# mixer-rx.net
KiCad netlist of a schematic drawn in Altium Designer
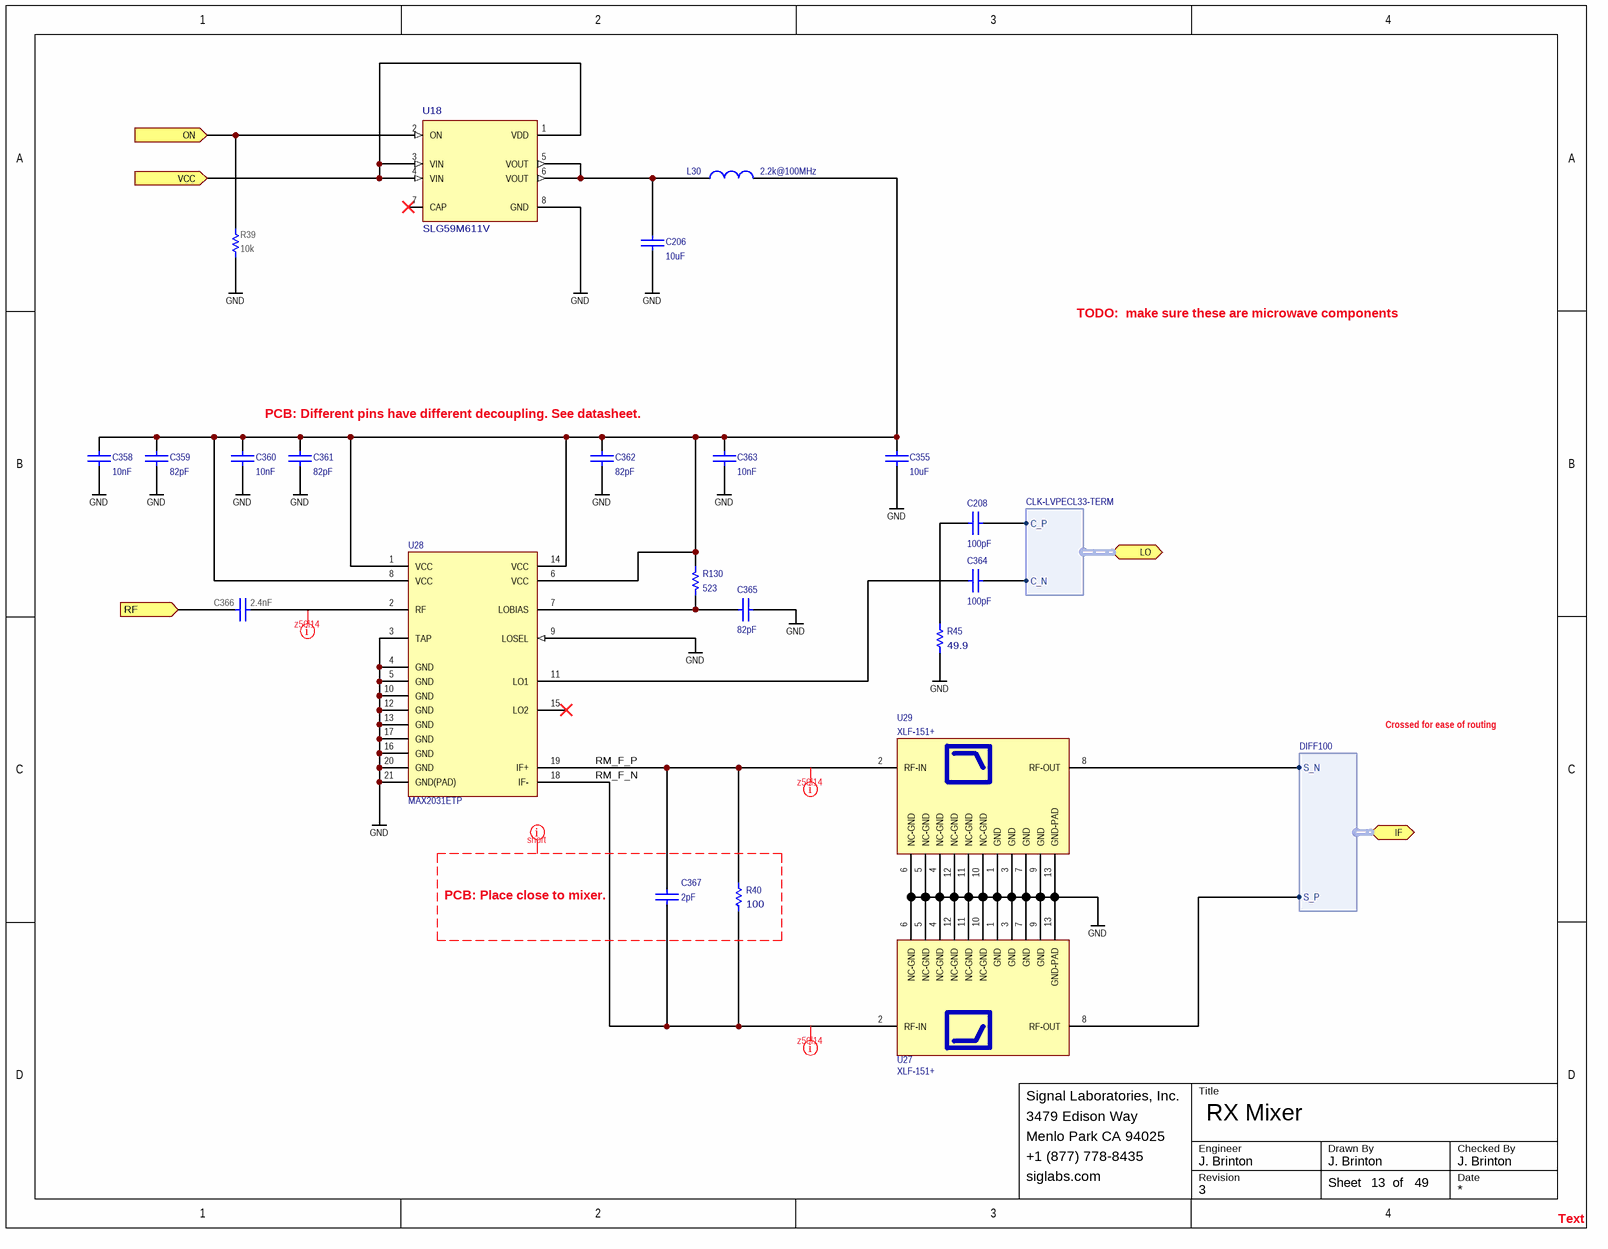
[diagram p0: mixer-rx.SchDoc]

(export (version "E")
  (design (tool "Eeschema 10.0.6"))
  (components
    (comp (ref "C206")
      (value "10uF")
      (footprint "CAPC160X80X90L20N")
      (description "Ceramic Capacitor 10uF ±20% 25V X5R 0603")
      (fields (field (name "MANUFACTURER") "Murata") (field (name "VOLTAGE") "25V"))
      (libsource (lib "generic") (part "CAP 0603"))
    )
    (comp (ref "C208")
      (value "100pF")
      (footprint "CAPC100X50X55L25N")
      (description "Ceramic Capacitor 100pF ±1% 25V NP0 0402")
      (fields (field (name "VOLTAGE") "25V") (field (name "MANUFACTURER") "Kemet"))
      (libsource (lib "generic") (part "CAP 0603"))
    )
    (comp (ref "C355")
      (value "10uF")
      (footprint "CAPC160X80X90L20N")
      (description "Ceramic Capacitor 10uF ±20% 25V X5R 0603")
      (fields (field (name "MANUFACTURER") "Murata") (field (name "VOLTAGE") "25V"))
      (libsource (lib "generic") (part "CAP 0603"))
    )
    (comp (ref "C358")
      (value "10nF")
      (footprint "CAPC100X50X55L25N")
      (description "Ceramic Capacitor 10nF ±10% 50V X7R 0402")
      (fields (field (name "VOLTAGE") "50V") (field (name "MANUFACTURER") "Murata"))
      (libsource (lib "Graviton") (part "CAP 0402"))
    )
    (comp (ref "C359")
      (value "82pF")
      (footprint "CAPC100X50X55L25N")
      (description "Ceramic Capacitor 82pF ±5% 25V NP0 0402")
      (fields (field (name "MANUFACTURER") "Vishay") (field (name "VOLTAGE") "25V"))
      (libsource (lib "generic") (part "CAP"))
    )
    (comp (ref "C360")
      (value "10nF")
      (footprint "CAPC100X50X55L25N")
      (description "Ceramic Capacitor 10nF ±10% 50V X7R 0402")
      (fields (field (name "VOLTAGE") "50V") (field (name "MANUFACTURER") "Murata"))
      (libsource (lib "Graviton") (part "CAP 0402"))
    )
    (comp (ref "C361")
      (value "82pF")
      (footprint "CAPC100X50X55L25N")
      (description "Ceramic Capacitor 82pF ±5% 25V NP0 0402")
      (fields (field (name "VOLTAGE") "25V") (field (name "MANUFACTURER") "Vishay"))
      (libsource (lib "generic") (part "CAP"))
    )
    (comp (ref "C362")
      (value "82pF")
      (footprint "CAPC100X50X55L25N")
      (description "Ceramic Capacitor 82pF ±5% 25V NP0 0402")
      (fields (field (name "MANUFACTURER") "Vishay") (field (name "VOLTAGE") "25V"))
      (libsource (lib "generic") (part "CAP"))
    )
    (comp (ref "C363")
      (value "10nF")
      (footprint "CAPC100X50X55L25N")
      (description "Ceramic Capacitor 10nF ±10% 50V X7R 0402")
      (fields (field (name "VOLTAGE") "50V") (field (name "MANUFACTURER") "Murata"))
      (libsource (lib "Graviton") (part "CAP 0402"))
    )
    (comp (ref "C364")
      (value "100pF")
      (footprint "CAPC100X50X55L25N")
      (description "Ceramic Capacitor 100pF ±1% 25V NP0 0402")
      (fields (field (name "VOLTAGE") "25V") (field (name "MANUFACTURER") "Kemet"))
      (libsource (lib "generic") (part "CAP 0603"))
    )
    (comp (ref "C365")
      (value "82pF")
      (footprint "CAPC100X50X55L25N")
      (description "Ceramic Capacitor 82pF ±5% 25V NP0 0402")
      (fields (field (name "VOLTAGE") "25V") (field (name "MANUFACTURER") "Vishay"))
      (libsource (lib "generic") (part "CAP"))
    )
    (comp (ref "C366")
      (value "2.4nF")
      (footprint "CAPC2012X145N")
      (description "Ceramic Capacitor 2.4nF 50V 0805")
      (fields (field (name "MANUFACTURER") "Dielectric Laboratories") (field (name "VOLTAGE") "50V"))
      (libsource (lib "") (part "CAP_1"))
    )
    (comp (ref "C367")
      (value "2pF")
      (footprint "CAPC100X50X55L25N")
      (description "Ceramic Capacitor 2pF ±0.25pF 50V NP0 0402")
      (fields (field (name "VOLTAGE") "50V") (field (name "MANUFACTURER") "Murata"))
      (libsource (lib "generic") (part "CAP 0402"))
    )
    (comp (ref "L30")
      (value "2.2k@100MHz")
      (footprint "INDC1005X55N")
      (description "Ferrite Bead 2.2k@100MHz 150mA 0402")
      (fields (field (name "MANUFACTURER") "TDK") (field (name "Comment") "MMZ1005A222ET000"))
      (libsource (lib "*") (part "INDUCTANCE1"))
    )
    (comp (ref "R39")
      (value "10k")
      (footprint "RESC1005X40N")
      (description "Thick Film Resistor 10k ±1% 0.1W 50V 0402")
      (fields (field (name "MANUFACTURER") "Panasonic") (field (name "TOLERANCE") "±1%"))
      (libsource (lib "generic") (part "RES"))
    )
    (comp (ref "R40")
      (value "100")
      (footprint "generic:RESC1608X55N")
      (description "Thin Film Resistor 100 Ohm ±0.5% 0603")
      (fields (field (name "MANUFACTURER") "Vishay") (field (name "TOLERANCE") "±0.5%"))
      (libsource (lib "Graviton") (part "RES 0603"))
    )
    (comp (ref "R45")
      (value "49.9")
      (footprint "generic:RESC1608X55N")
      (description "Thin Film Resistor 49.9 Ohm ±0.5% 0603")
      (fields (field (name "MANUFACTURER") "Vishay") (field (name "TOLERANCE") "±0.5%"))
      (libsource (lib "Graviton") (part "RES 0603"))
    )
    (comp (ref "R130")
      (value "523")
      (footprint "RESC1005X40N")
      (description "Thin Film Resistor 523 ±0.1% 0402")
      (fields (field (name "MANUFACTURER") "Panasonic") (field (name "TOLERANCE") "±0.1%"))
      (libsource (lib "Graviton") (part "RES 0402"))
    )
    (comp (ref "U18")
      (value "SLG59M611V")
      (footprint "DFN200X150X80-8N")
      (description "High-Side Load Switch")
      (fields (field (name "MANUFACTURER") "Silego"))
      (libsource (lib "silego") (part "SLG59M611V"))
    )
    (comp (ref "U27")
      (value "XLF-151+")
      (footprint "QFN-XLF-12")
      (description "Reflectionless Low-Pass Filter, DC-150Mhz")
      (fields (field (name "MANUFACTURER") "Mini-Circuits"))
      (libsource (lib "") (part "XLF-151+_1"))
    )
    (comp (ref "U28")
      (value "MAX2031ETP")
      (footprint "QFN21P65_500X500X80L55X30T320N")
      (description "Upconversion/Downconversion Mixer")
      (fields (field (name "MANUFACTURER") "Maxim"))
      (libsource (lib "maxim") (part "MAX2031ETP"))
    )
    (comp (ref "U29")
      (value "XLF-151+")
      (footprint "QFN-XLF-12")
      (description "Reflectionless Low-Pass Filter, DC-150Mhz")
      (fields (field (name "MANUFACTURER") "Mini-Circuits"))
      (libsource (lib "Mini-Circuits") (part "XLF-151+"))
    )
  )
  (nets
    (net (code "3") (name "/C_N") (class "Default")
      (node (ref "C364") (pin "2") (pinfunction "2_2") (pintype "passive"))
    )
    (net (code "4") (name "/C_P") (class "Default")
      (node (ref "C208") (pin "2") (pinfunction "2_2") (pintype "passive"))
    )
    (net (code "5") (name "/ON") (class "Default")
      (node (ref "R39") (pin "2") (pinfunction "2_2") (pintype "passive"))
      (node (ref "U18") (pin "2") (pinfunction "ON_2") (pintype "input"))
    )
    (net (code "6") (name "/RF") (class "Default")
      (node (ref "C366") (pin "2") (pinfunction "2_2") (pintype "passive"))
    )
    (net (code "7") (name "/RM_F_N") (class "Default")
      (node (ref "C367") (pin "1") (pinfunction "1_1") (pintype "passive"))
      (node (ref "R40") (pin "1") (pinfunction "1_1") (pintype "passive"))
      (node (ref "U27") (pin "2") (pinfunction "RF-IN_2") (pintype "passive"))
      (node (ref "U28") (pin "18") (pinfunction "IF-_18") (pintype "passive"))
    )
    (net (code "8") (name "/RM_F_P") (class "Default")
      (node (ref "C367") (pin "2") (pinfunction "2_2") (pintype "passive"))
      (node (ref "R40") (pin "2") (pinfunction "2_2") (pintype "passive"))
      (node (ref "U28") (pin "19") (pinfunction "IF+_19") (pintype "passive"))
      (node (ref "U29") (pin "2") (pinfunction "RF-IN_2") (pintype "passive"))
    )
    (net (code "9") (name "/S_N") (class "Default")
      (node (ref "U29") (pin "8") (pinfunction "RF-OUT_8") (pintype "passive"))
    )
    (net (code "10") (name "/S_P") (class "Default")
      (node (ref "U27") (pin "8") (pinfunction "RF-OUT_8") (pintype "passive"))
    )
    (net (code "11") (name "/VCC") (class "Default")
      (node (ref "U18") (pin "1") (pinfunction "VDD_1") (pintype "power_in"))
      (node (ref "U18") (pin "3") (pinfunction "VIN_3") (pintype "input"))
      (node (ref "U18") (pin "4") (pinfunction "VIN_4") (pintype "input"))
    )
    (net (code "14") (name "GND") (class "Default")
      (node (ref "C206") (pin "1") (pinfunction "1_1") (pintype "passive"))
      (node (ref "C355") (pin "1") (pinfunction "1_1") (pintype "passive"))
      (node (ref "C358") (pin "1") (pinfunction "1_1") (pintype "passive"))
      (node (ref "C359") (pin "1") (pinfunction "1_1") (pintype "passive"))
      (node (ref "C360") (pin "1") (pinfunction "1_1") (pintype "passive"))
      (node (ref "C361") (pin "1") (pinfunction "1_1") (pintype "passive"))
      (node (ref "C362") (pin "1") (pinfunction "1_1") (pintype "passive"))
      (node (ref "C363") (pin "1") (pinfunction "1_1") (pintype "passive"))
      (node (ref "C365") (pin "2") (pinfunction "2_2") (pintype "passive"))
      (node (ref "R39") (pin "1") (pinfunction "1_1") (pintype "passive"))
      (node (ref "R45") (pin "1") (pinfunction "1_1") (pintype "passive"))
      (node (ref "U18") (pin "8") (pinfunction "GND_8") (pintype "power_in"))
      (node (ref "U27") (pin "1") (pinfunction "GND_1") (pintype "passive"))
      (node (ref "U27") (pin "10") (pinfunction "NC-GND_10") (pintype "passive"))
      (node (ref "U27") (pin "11") (pinfunction "NC-GND_11") (pintype "passive"))
      (node (ref "U27") (pin "12") (pinfunction "NC-GND_12") (pintype "passive"))
      (node (ref "U27") (pin "13") (pinfunction "GND-PAD_13") (pintype "passive"))
      (node (ref "U27") (pin "3") (pinfunction "GND_3") (pintype "passive"))
      (node (ref "U27") (pin "4") (pinfunction "NC-GND_4") (pintype "passive"))
      (node (ref "U27") (pin "5") (pinfunction "NC-GND_5") (pintype "passive"))
      (node (ref "U27") (pin "6") (pinfunction "NC-GND_6") (pintype "passive"))
      (node (ref "U27") (pin "7") (pinfunction "GND_7") (pintype "passive"))
      (node (ref "U27") (pin "9") (pinfunction "GND_9") (pintype "passive"))
      (node (ref "U28") (pin "10") (pinfunction "GND_10") (pintype "power_in"))
      (node (ref "U28") (pin "12") (pinfunction "GND_12") (pintype "power_in"))
      (node (ref "U28") (pin "13") (pinfunction "GND_13") (pintype "power_in"))
      (node (ref "U28") (pin "16") (pinfunction "GND_16") (pintype "power_in"))
      (node (ref "U28") (pin "17") (pinfunction "GND_17") (pintype "power_in"))
      (node (ref "U28") (pin "20") (pinfunction "GND_20") (pintype "power_in"))
      (node (ref "U28") (pin "21") (pinfunction "GND(PAD)_21") (pintype "power_in"))
      (node (ref "U28") (pin "3") (pinfunction "TAP_3") (pintype "passive"))
      (node (ref "U28") (pin "4") (pinfunction "GND_4") (pintype "power_in"))
      (node (ref "U28") (pin "5") (pinfunction "GND_5") (pintype "power_in"))
      (node (ref "U28") (pin "9") (pinfunction "LOSEL_9") (pintype "input"))
      (node (ref "U29") (pin "1") (pinfunction "GND_1") (pintype "passive"))
      (node (ref "U29") (pin "10") (pinfunction "NC-GND_10") (pintype "passive"))
      (node (ref "U29") (pin "11") (pinfunction "NC-GND_11") (pintype "passive"))
      (node (ref "U29") (pin "12") (pinfunction "NC-GND_12") (pintype "passive"))
      (node (ref "U29") (pin "13") (pinfunction "GND-PAD_13") (pintype "passive"))
      (node (ref "U29") (pin "3") (pinfunction "GND_3") (pintype "passive"))
      (node (ref "U29") (pin "4") (pinfunction "NC-GND_4") (pintype "passive"))
      (node (ref "U29") (pin "5") (pinfunction "NC-GND_5") (pintype "passive"))
      (node (ref "U29") (pin "6") (pinfunction "NC-GND_6") (pintype "passive"))
      (node (ref "U29") (pin "7") (pinfunction "GND_7") (pintype "passive"))
      (node (ref "U29") (pin "9") (pinfunction "GND_9") (pintype "passive"))
    )
    (net (code "15") (name "Net-(C206-Pad2)") (class "Default")
      (node (ref "C206") (pin "2") (pinfunction "2_2") (pintype "passive"))
      (node (ref "L30") (pin "1") (pinfunction "1_1") (pintype "passive"))
      (node (ref "U18") (pin "5") (pinfunction "VOUT_5") (pintype "output"))
      (node (ref "U18") (pin "6") (pinfunction "VOUT_6") (pintype "output"))
    )
    (net (code "16") (name "Net-(C208-Pad1)") (class "Default")
      (node (ref "C208") (pin "1") (pinfunction "1_1") (pintype "passive"))
      (node (ref "R45") (pin "2") (pinfunction "2_2") (pintype "passive"))
    )
    (net (code "17") (name "Net-(C355-Pad2)") (class "Default")
      (node (ref "C355") (pin "2") (pinfunction "2_2") (pintype "passive"))
      (node (ref "C358") (pin "2") (pinfunction "2_2") (pintype "passive"))
      (node (ref "C359") (pin "2") (pinfunction "2_2") (pintype "passive"))
      (node (ref "C360") (pin "2") (pinfunction "2_2") (pintype "passive"))
      (node (ref "C361") (pin "2") (pinfunction "2_2") (pintype "passive"))
      (node (ref "C362") (pin "2") (pinfunction "2_2") (pintype "passive"))
      (node (ref "C363") (pin "2") (pinfunction "2_2") (pintype "passive"))
      (node (ref "L30") (pin "2") (pinfunction "2_2") (pintype "passive"))
      (node (ref "R130") (pin "2") (pinfunction "2_2") (pintype "passive"))
      (node (ref "U28") (pin "1") (pinfunction "VCC_1") (pintype "power_in"))
      (node (ref "U28") (pin "14") (pinfunction "VCC_14") (pintype "power_in"))
      (node (ref "U28") (pin "6") (pinfunction "VCC_6") (pintype "power_in"))
      (node (ref "U28") (pin "8") (pinfunction "VCC_8") (pintype "power_in"))
    )
    (net (code "18") (name "Net-(U28-LO1)") (class "Default")
      (node (ref "C364") (pin "1") (pinfunction "1_1") (pintype "passive"))
      (node (ref "U28") (pin "11") (pinfunction "LO1_11") (pintype "passive"))
    )
    (net (code "19") (name "Net-(U28-LOBIAS)") (class "Default")
      (node (ref "C365") (pin "1") (pinfunction "1_1") (pintype "passive"))
      (node (ref "R130") (pin "1") (pinfunction "1_1") (pintype "passive"))
      (node (ref "U28") (pin "7") (pinfunction "LOBIAS_7") (pintype "passive"))
    )
    (net (code "20") (name "Net-(U28-RF)") (class "Default")
      (node (ref "C366") (pin "1") (pinfunction "1_1") (pintype "passive"))
      (node (ref "U28") (pin "2") (pinfunction "RF_2") (pintype "passive"))
    )
    (net (code "21") (name "unconnected-(U18-CAP-Pad7)") (class "Default")
      (node (ref "U18") (pin "7") (pinfunction "CAP_7") (pintype "passive+no_connect"))
    )
    (net (code "22") (name "unconnected-(U28-LO2-Pad15)") (class "Default")
      (node (ref "U28") (pin "15") (pinfunction "LO2_15") (pintype "passive+no_connect"))
    )
  )
)
